# fly.net
KiCad netlist of a schematic drawn in Altium Designer
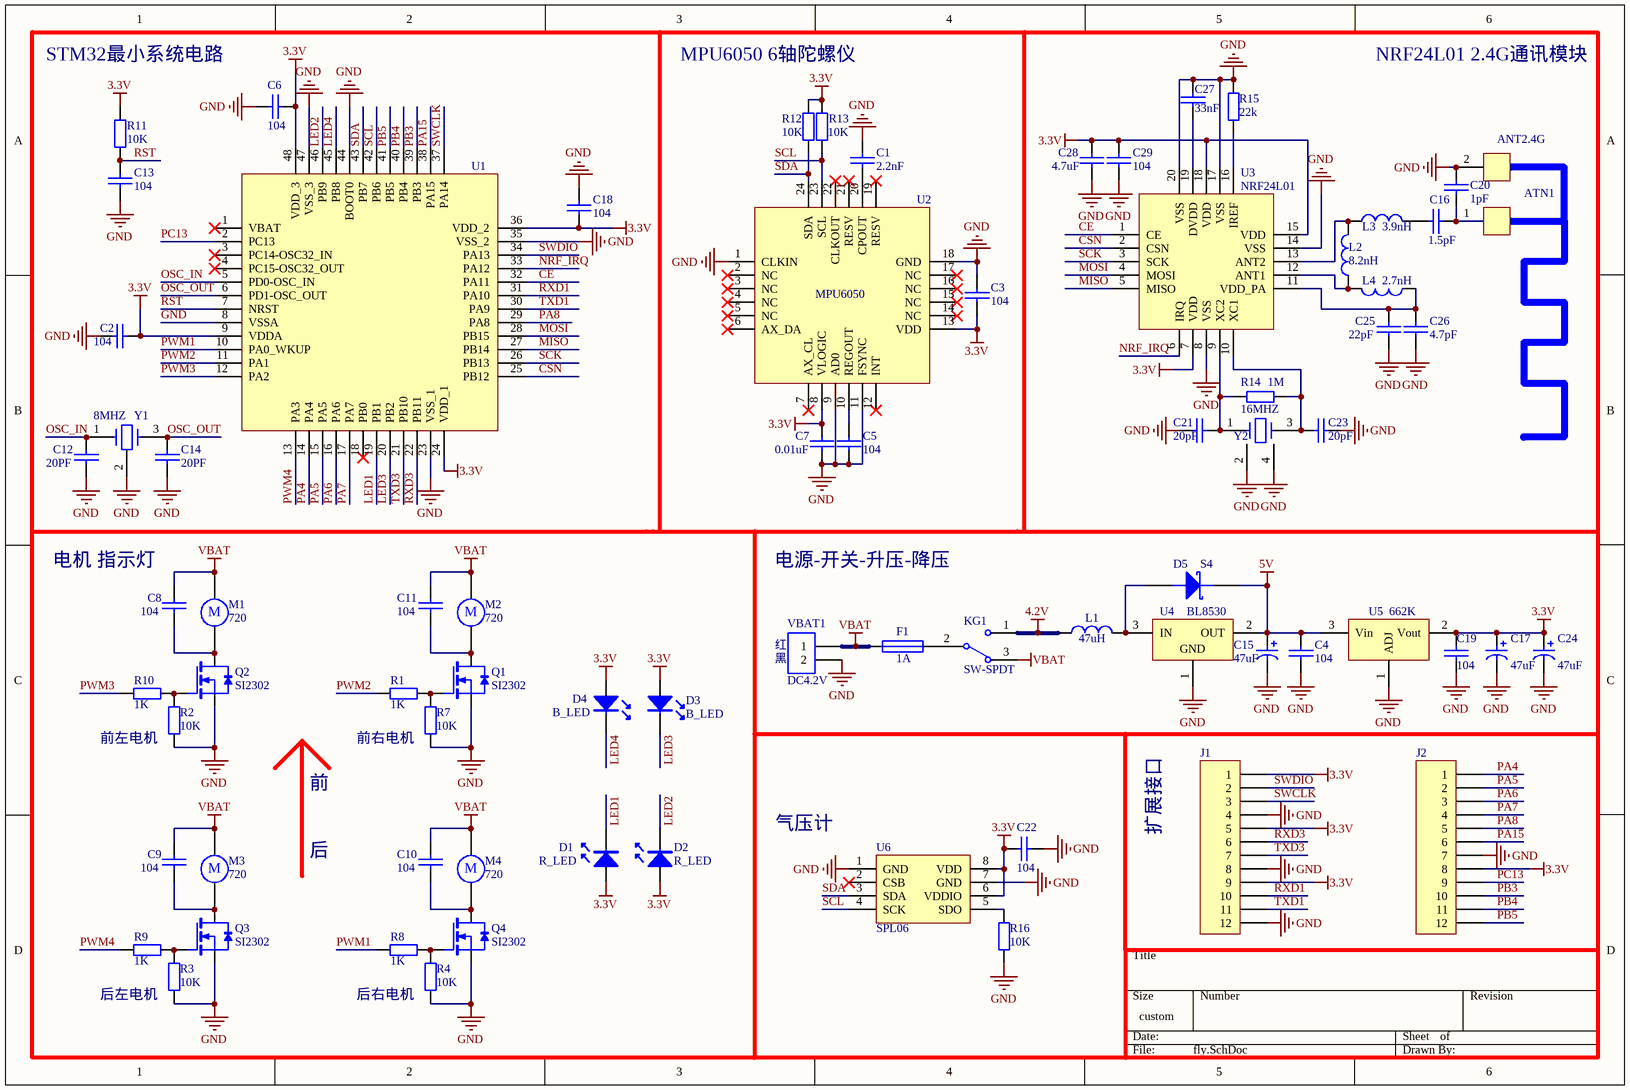
[diagram p0: fly.SchDoc]

(export (version "E")
  (design (tool "Eeschema 10.0.6"))
  (components
    (comp (ref "ATN1") (value "ANT2.4G") (footprint "ANT2.4G_1") (libsource (lib "fly") (part "ANT2.4G_2")))
    (comp (ref "C1")
      (value "2.2nF")
      (footprint "C_0603")
      (description "Capacitor")
      (libsource (lib "fly") (part "CAP"))
    )
    (comp (ref "C2")
      (value "104")
      (footprint "C_0603")
      (description "Capacitor")
      (libsource (lib "fly") (part "CAP"))
    )
    (comp (ref "C3")
      (value "104")
      (footprint "C_0603")
      (description "Capacitor")
      (libsource (lib "fly") (part "CAP"))
    )
    (comp (ref "C4")
      (value "104")
      (footprint "C_0603")
      (description "Capacitor")
      (libsource (lib "fly") (part "CAP"))
    )
    (comp (ref "C5")
      (value "104")
      (footprint "C_0603")
      (description "Capacitor")
      (libsource (lib "fly") (part "CAP"))
    )
    (comp (ref "C6")
      (value "104")
      (footprint "C_0603")
      (description "Capacitor")
      (libsource (lib "fly") (part "CAP"))
    )
    (comp (ref "C7")
      (value "0.01uF")
      (footprint "C_0603")
      (description "Capacitor")
      (libsource (lib "fly") (part "CAP"))
    )
    (comp (ref "C8")
      (value "104")
      (footprint "C_0603")
      (description "Capacitor")
      (libsource (lib "fly") (part "CAP"))
    )
    (comp (ref "C9")
      (value "104")
      (footprint "C_0603")
      (description "Capacitor")
      (libsource (lib "fly") (part "CAP"))
    )
    (comp (ref "C10")
      (value "104")
      (footprint "C_0603")
      (description "Capacitor")
      (libsource (lib "fly") (part "CAP"))
    )
    (comp (ref "C11")
      (value "104")
      (footprint "C_0603")
      (description "Capacitor")
      (libsource (lib "fly") (part "CAP"))
    )
    (comp (ref "C12")
      (value "20PF")
      (footprint "C_0603")
      (description "Capacitor")
      (libsource (lib "fly") (part "CAP"))
    )
    (comp (ref "C13")
      (value "104")
      (footprint "C_0603")
      (description "Capacitor")
      (libsource (lib "fly") (part "CAP"))
    )
    (comp (ref "C14")
      (value "20PF")
      (footprint "C_0603")
      (description "Capacitor")
      (libsource (lib "fly") (part "CAP"))
    )
    (comp (ref "C15")
      (value "47uF")
      (footprint "C_1206")
      (description "Polarized Capacitor (Radial)")
      (fields (field (name "PUBLISHER") "Altium Limited"))
      (libsource (lib "fly") (part "Cap Pol"))
    )
    (comp (ref "C16")
      (value "1.5pF")
      (footprint "C_0603")
      (description "Capacitor")
      (libsource (lib "fly") (part "CAP"))
    )
    (comp (ref "C17")
      (value "47uF")
      (footprint "C_1206")
      (description "Polarized Capacitor (Radial)")
      (fields (field (name "PUBLISHER") "Altium Limited"))
      (libsource (lib "fly") (part "Cap Pol"))
    )
    (comp (ref "C18")
      (value "104")
      (footprint "C_0603")
      (description "Capacitor")
      (libsource (lib "fly") (part "CAP"))
    )
    (comp (ref "C19")
      (value "104")
      (footprint "C_0603")
      (description "Capacitor")
      (libsource (lib "fly") (part "CAP"))
    )
    (comp (ref "C20")
      (value "1pF")
      (footprint "C_0603")
      (description "Capacitor")
      (libsource (lib "fly") (part "CAP"))
    )
    (comp (ref "C21")
      (value "20pF")
      (footprint "C_0603")
      (description "Capacitor")
      (libsource (lib "fly") (part "CAP"))
    )
    (comp (ref "C22")
      (value "104")
      (footprint "C_0603")
      (description "Capacitor")
      (libsource (lib "fly") (part "CAP"))
    )
    (comp (ref "C23")
      (value "20pF")
      (footprint "C_0603")
      (description "Capacitor")
      (libsource (lib "fly") (part "CAP"))
    )
    (comp (ref "C24")
      (value "47uF")
      (footprint "C_1206")
      (description "Polarized Capacitor (Radial)")
      (fields (field (name "PUBLISHER") "Altium Limited"))
      (libsource (lib "fly") (part "Cap Pol"))
    )
    (comp (ref "C25")
      (value "22pF")
      (footprint "C_0603")
      (description "Capacitor")
      (libsource (lib "fly") (part "CAP"))
    )
    (comp (ref "C26")
      (value "4.7pF")
      (footprint "C_0603")
      (description "Capacitor")
      (libsource (lib "fly") (part "CAP"))
    )
    (comp (ref "C27")
      (value "33nF")
      (footprint "C_0603")
      (description "Capacitor")
      (libsource (lib "fly") (part "CAP"))
    )
    (comp (ref "C28")
      (value "4.7uF")
      (footprint "C_0603")
      (description "Capacitor")
      (libsource (lib "fly") (part "CAP"))
    )
    (comp (ref "C29")
      (value "104")
      (footprint "C_0603")
      (description "Capacitor")
      (libsource (lib "fly") (part "CAP"))
    )
    (comp (ref "D1") (value "R_LED") (footprint "LED0603") (libsource (lib "fly") (part "LED")))
    (comp (ref "D2") (value "R_LED") (footprint "LED0603") (libsource (lib "fly") (part "LED")))
    (comp (ref "D3") (value "B_LED") (footprint "LED0603") (libsource (lib "fly") (part "LED")))
    (comp (ref "D4") (value "B_LED") (footprint "LED0603") (libsource (lib "fly") (part "LED")))
    (comp (ref "D5")
      (value "S4")
      (footprint "SOD-123")
      (description "Schottky Diode")
      (libsource (lib "fly") (part "DIODE SCHOTTKY"))
    )
    (comp (ref "F1")
      (value "1A")
      (footprint "FU 0805")
      (description "Fuse")
      (libsource (lib "fly") (part "FUSE1"))
    )
    (comp (ref "J1")
      (value "12P 2.54MM")
      (footprint "HDR2.54-LI-12P")
      (description "Header, 8-Pin")
      (fields (field (name "PUBLISHER") "Altium Limited"))
      (libsource (lib "fly") (part "Header 12"))
    )
    (comp (ref "J2")
      (value "12P 2.54MM")
      (footprint "HDR2.54-LI-12P")
      (description "Header, 8-Pin")
      (fields (field (name "PUBLISHER") "Altium Limited"))
      (libsource (lib "fly") (part "Header 12"))
    )
    (comp (ref "KG1")
      (value "SW-SPDT")
      (footprint "TPKG")
      (description "SPDT Subminiature Toggle Switch, Right Angle Mounting, Vertical Actuation")
      (fields (field (name "PUBLISHER") "Altium Limited"))
      (libsource (lib "fly") (part "SW-SPDT"))
    )
    (comp (ref "L1")
      (value "47uH")
      (footprint "L_CD43")
      (description "Inductor")
      (fields (field (name "PUBLISHER") "Altium Limited"))
      (libsource (lib "fly") (part "Inductor Chip"))
    )
    (comp (ref "L2")
      (value "8.2nH")
      (footprint "L_0603")
      (description "Inductor")
      (fields (field (name "PUBLISHER") "Altium Limited"))
      (libsource (lib "fly") (part "Inductor Chip"))
    )
    (comp (ref "L3")
      (value "3.9nH")
      (footprint "L_0603")
      (description "Inductor")
      (fields (field (name "PUBLISHER") "Altium Limited"))
      (libsource (lib "fly") (part "Inductor Chip"))
    )
    (comp (ref "L4")
      (value "2.7nH")
      (footprint "L_0603")
      (description "Inductor")
      (fields (field (name "PUBLISHER") "Altium Limited"))
      (libsource (lib "fly") (part "Inductor Chip"))
    )
    (comp (ref "M1")
      (value "720")
      (footprint "HDR2.54-LI-2P")
      (description "Motor, General Kind")
      (fields (field (name "PUBLISHER") "Altium Limited"))
      (libsource (lib "fly") (part "Motor"))
    )
    (comp (ref "M2")
      (value "720")
      (footprint "HDR2.54-LI-2P")
      (description "Motor, General Kind")
      (fields (field (name "PUBLISHER") "Altium Limited"))
      (libsource (lib "fly") (part "Motor"))
    )
    (comp (ref "M3")
      (value "720")
      (footprint "HDR2.54-LI-2P")
      (description "Motor, General Kind")
      (fields (field (name "PUBLISHER") "Altium Limited"))
      (libsource (lib "fly") (part "Motor"))
    )
    (comp (ref "M4")
      (value "720")
      (footprint "HDR2.54-LI-2P")
      (description "Motor, General Kind")
      (fields (field (name "PUBLISHER") "Altium Limited"))
      (libsource (lib "fly") (part "Motor"))
    )
    (comp (ref "Q1")
      (value "SI2302")
      (footprint "SOT23")
      (description "N-Channel MOSFET")
      (libsource (lib "fly") (part "N_MOS"))
    )
    (comp (ref "Q2")
      (value "SI2302")
      (footprint "SOT23")
      (description "N-Channel MOSFET")
      (libsource (lib "fly") (part "N_MOS"))
    )
    (comp (ref "Q3")
      (value "SI2302")
      (footprint "SOT23")
      (description "N-Channel MOSFET")
      (libsource (lib "fly") (part "N_MOS"))
    )
    (comp (ref "Q4")
      (value "SI2302")
      (footprint "SOT23")
      (description "N-Channel MOSFET")
      (libsource (lib "fly") (part "N_MOS"))
    )
    (comp (ref "R1")
      (value "1K")
      (footprint "R_0603")
      (description "Resistor")
      (fields (field (name "PUBLISHER") "Altium Limited"))
      (libsource (lib "") (part "Res2_1"))
    )
    (comp (ref "R2")
      (value "10K")
      (footprint "R_0603")
      (description "Resistor")
      (fields (field (name "PUBLISHER") "Altium Limited"))
      (libsource (lib "fly") (part "Res2"))
    )
    (comp (ref "R3")
      (value "10K")
      (footprint "R_0603")
      (description "Resistor")
      (fields (field (name "PUBLISHER") "Altium Limited"))
      (libsource (lib "fly") (part "Res2"))
    )
    (comp (ref "R4")
      (value "10K")
      (footprint "R_0603")
      (description "Resistor")
      (fields (field (name "PUBLISHER") "Altium Limited"))
      (libsource (lib "fly") (part "Res2"))
    )
    (comp (ref "R7")
      (value "10K")
      (footprint "R_0603")
      (description "Resistor")
      (fields (field (name "PUBLISHER") "Altium Limited"))
      (libsource (lib "fly") (part "Res2"))
    )
    (comp (ref "R8")
      (value "1K")
      (footprint "R_0603")
      (description "Resistor")
      (fields (field (name "PUBLISHER") "Altium Limited"))
      (libsource (lib "") (part "Res2_1"))
    )
    (comp (ref "R9")
      (value "1K")
      (footprint "R_0603")
      (description "Resistor")
      (fields (field (name "PUBLISHER") "Altium Limited"))
      (libsource (lib "") (part "Res2_1"))
    )
    (comp (ref "R10")
      (value "1K")
      (footprint "R_0603")
      (description "Resistor")
      (fields (field (name "PUBLISHER") "Altium Limited"))
      (libsource (lib "") (part "Res2_1"))
    )
    (comp (ref "R11")
      (value "10K")
      (footprint "R_0603")
      (description "Resistor")
      (fields (field (name "PUBLISHER") "Altium Limited"))
      (libsource (lib "fly") (part "Res2"))
    )
    (comp (ref "R12")
      (value "10K")
      (footprint "R_0603")
      (description "Resistor")
      (fields (field (name "PUBLISHER") "Altium Limited"))
      (libsource (lib "fly") (part "Res2"))
    )
    (comp (ref "R13")
      (value "10K")
      (footprint "R_0603")
      (description "Resistor")
      (fields (field (name "PUBLISHER") "Altium Limited"))
      (libsource (lib "fly") (part "Res2"))
    )
    (comp (ref "R14")
      (value "1M")
      (footprint "R_0603")
      (description "Resistor")
      (fields (field (name "PUBLISHER") "Altium Limited"))
      (libsource (lib "") (part "Res2_1"))
    )
    (comp (ref "R15")
      (value "22k")
      (footprint "R_0603")
      (description "Resistor")
      (fields (field (name "PUBLISHER") "Altium Limited"))
      (libsource (lib "fly") (part "Res2"))
    )
    (comp (ref "R16")
      (value "10K")
      (footprint "R_0603")
      (description "Resistor")
      (fields (field (name "PUBLISHER") "Altium Limited"))
      (libsource (lib "") (part "Res2_2"))
    )
    (comp (ref "U1")
      (value "STM32F103C8T6_LQFP48")
      (footprint "LQFP48_STM32")
      (libsource (lib "fly") (part "STM32_LQFP48"))
    )
    (comp (ref "U2") (value "MPU6050") (footprint "QFN24") (libsource (lib "fly") (part "MPU6050")))
    (comp (ref "U3") (value "NRF24L01") (footprint "LQFP32") (libsource (lib "fly") (part "NRF24L01")))
    (comp (ref "U4")
      (value "BL8530")
      (footprint "SOT-89")
      (description "POSITIVE OUTPUT VOLTAGE")
      (libsource (lib "fly") (part "HT7750"))
    )
    (comp (ref "U5")
      (value "662K")
      (footprint "SOT23-PIN132")
      (description "3-Terminal Adjustable Positive Voltage Regulator")
      (libsource (lib "fly") (part "LM317"))
    )
    (comp (ref "U6") (value "SPL06") (footprint "SMD_SPL06") (libsource (lib "fly") (part "SPL06")))
    (comp (ref "VBAT1")
      (value "DC4.2V")
      (footprint "HDR2.54-WI-2P")
      (description "Connector")
      (libsource (lib "fly") (part "CON2"))
    )
    (comp (ref "Y1") (value "8MHZ") (footprint "Y3213") (libsource (lib "fly") (part "Y")))
    (comp (ref "Y2") (value "16MHZ") (footprint "OSC 3225-4P") (libsource (lib "fly") (part "Y_1")))
  )
  (nets
    (net (code "1") (name "/CE") (class "Default")
      (node (ref "U1") (pin "32") (pinfunction "PA11_32") (pintype "passive"))
      (node (ref "U3") (pin "1") (pinfunction "CE_1") (pintype "power_in"))
    )
    (net (code "2") (name "/CSN") (class "Default")
      (node (ref "U1") (pin "25") (pinfunction "PB12_25") (pintype "passive"))
      (node (ref "U3") (pin "2") (pinfunction "CSN_2") (pintype "power_in"))
    )
    (net (code "3") (name "/LED1") (class "Default")
      (node (ref "D1") (pin "2") (pinfunction "2_2") (pintype "passive"))
      (node (ref "U1") (pin "19") (pinfunction "PB1_19") (pintype "passive"))
    )
    (net (code "4") (name "/LED2") (class "Default")
      (node (ref "D2") (pin "2") (pinfunction "2_2") (pintype "passive"))
      (node (ref "U1") (pin "46") (pinfunction "PB9_46") (pintype "passive"))
    )
    (net (code "5") (name "/LED3") (class "Default")
      (node (ref "D3") (pin "2") (pinfunction "2_2") (pintype "passive"))
      (node (ref "U1") (pin "20") (pinfunction "PB2_20") (pintype "passive"))
    )
    (net (code "6") (name "/LED4") (class "Default")
      (node (ref "D4") (pin "2") (pinfunction "2_2") (pintype "passive"))
      (node (ref "U1") (pin "45") (pinfunction "PB8_45") (pintype "passive"))
    )
    (net (code "7") (name "/MISO") (class "Default")
      (node (ref "U1") (pin "27") (pinfunction "PB14_27") (pintype "passive"))
      (node (ref "U3") (pin "5") (pinfunction "MISO_5") (pintype "power_in"))
    )
    (net (code "8") (name "/MOSI") (class "Default")
      (node (ref "U1") (pin "28") (pinfunction "PB15_28") (pintype "passive"))
      (node (ref "U3") (pin "4") (pinfunction "MOSI_4") (pintype "power_in"))
    )
    (net (code "9") (name "/NRF_IRQ") (class "Default")
      (node (ref "U1") (pin "33") (pinfunction "PA12_33") (pintype "passive"))
      (node (ref "U3") (pin "6") (pinfunction "IRQ_6") (pintype "power_in"))
    )
    (net (code "10") (name "/OSC_IN") (class "Default")
      (node (ref "C12") (pin "1") (pinfunction "1_1") (pintype "passive"))
      (node (ref "U1") (pin "5") (pinfunction "PD0-OSC_IN_5") (pintype "passive"))
      (node (ref "Y1") (pin "1") (pinfunction "1_1") (pintype "passive"))
    )
    (net (code "11") (name "/OSC_OUT") (class "Default")
      (node (ref "C14") (pin "2") (pinfunction "2_2") (pintype "passive"))
      (node (ref "U1") (pin "6") (pinfunction "PD1-OSC_OUT_6") (pintype "passive"))
      (node (ref "Y1") (pin "3") (pinfunction "3_3") (pintype "passive"))
    )
    (net (code "12") (name "/PA4") (class "Default")
      (node (ref "J2") (pin "1") (pinfunction "1_1") (pintype "passive"))
      (node (ref "U1") (pin "14") (pinfunction "PA4_14") (pintype "passive"))
    )
    (net (code "13") (name "/PA5") (class "Default")
      (node (ref "J2") (pin "2") (pinfunction "2_2") (pintype "passive"))
      (node (ref "U1") (pin "15") (pinfunction "PA5_15") (pintype "passive"))
    )
    (net (code "14") (name "/PA6") (class "Default")
      (node (ref "J2") (pin "3") (pinfunction "3_3") (pintype "passive"))
      (node (ref "U1") (pin "16") (pinfunction "PA6_16") (pintype "passive"))
    )
    (net (code "15") (name "/PA7") (class "Default")
      (node (ref "J2") (pin "4") (pinfunction "4_4") (pintype "passive"))
      (node (ref "U1") (pin "17") (pinfunction "PA7_17") (pintype "passive"))
    )
    (net (code "16") (name "/PA8") (class "Default")
      (node (ref "J2") (pin "5") (pinfunction "5_5") (pintype "passive"))
      (node (ref "U1") (pin "29") (pinfunction "PA8_29") (pintype "passive"))
    )
    (net (code "17") (name "/PA15") (class "Default")
      (node (ref "J2") (pin "6") (pinfunction "6_6") (pintype "passive"))
      (node (ref "U1") (pin "38") (pinfunction "PA15_38") (pintype "passive"))
    )
    (net (code "18") (name "/PB3") (class "Default")
      (node (ref "J2") (pin "10") (pinfunction "10_10") (pintype "passive"))
      (node (ref "U1") (pin "39") (pinfunction "PB3_39") (pintype "passive"))
    )
    (net (code "19") (name "/PB4") (class "Default")
      (node (ref "J2") (pin "11") (pinfunction "11_11") (pintype "passive"))
      (node (ref "U1") (pin "40") (pinfunction "PB4_40") (pintype "passive"))
    )
    (net (code "20") (name "/PB5") (class "Default")
      (node (ref "J2") (pin "12") (pinfunction "12_12") (pintype "passive"))
      (node (ref "U1") (pin "41") (pinfunction "PB5_41") (pintype "passive"))
    )
    (net (code "21") (name "/PC13") (class "Default")
      (node (ref "J2") (pin "9") (pinfunction "9_9") (pintype "passive"))
      (node (ref "U1") (pin "2") (pinfunction "PC13_2") (pintype "passive"))
    )
    (net (code "22") (name "/PWM1") (class "Default")
      (node (ref "R8") (pin "2") (pinfunction "2_2") (pintype "passive"))
      (node (ref "U1") (pin "10") (pinfunction "PA0_WKUP_10") (pintype "passive"))
    )
    (net (code "23") (name "/PWM2") (class "Default")
      (node (ref "R1") (pin "2") (pinfunction "2_2") (pintype "passive"))
      (node (ref "U1") (pin "11") (pinfunction "PA1_11") (pintype "passive"))
    )
    (net (code "24") (name "/PWM3") (class "Default")
      (node (ref "R10") (pin "2") (pinfunction "2_2") (pintype "passive"))
      (node (ref "U1") (pin "12") (pinfunction "PA2_12") (pintype "passive"))
    )
    (net (code "25") (name "/PWM4") (class "Default")
      (node (ref "R9") (pin "2") (pinfunction "2_2") (pintype "passive"))
      (node (ref "U1") (pin "13") (pinfunction "PA3_13") (pintype "passive"))
    )
    (net (code "26") (name "/RST") (class "Default")
      (node (ref "C13") (pin "1") (pinfunction "1_1") (pintype "passive"))
      (node (ref "R11") (pin "1") (pinfunction "1_1") (pintype "passive"))
      (node (ref "U1") (pin "7") (pinfunction "NRST_7") (pintype "passive"))
    )
    (net (code "27") (name "/RXD1") (class "Default")
      (node (ref "J1") (pin "10") (pinfunction "10_10") (pintype "passive"))
      (node (ref "U1") (pin "31") (pinfunction "PA10_31") (pintype "passive"))
    )
    (net (code "28") (name "/RXD3") (class "Default")
      (node (ref "J1") (pin "6") (pinfunction "6_6") (pintype "passive"))
      (node (ref "U1") (pin "22") (pinfunction "PB11_22") (pintype "passive"))
    )
    (net (code "29") (name "/SCK") (class "Default")
      (node (ref "U1") (pin "26") (pinfunction "PB13_26") (pintype "passive"))
      (node (ref "U3") (pin "3") (pinfunction "SCK_3") (pintype "power_in"))
    )
    (net (code "30") (name "/SCL") (class "Default")
      (node (ref "R13") (pin "1") (pinfunction "1_1") (pintype "passive"))
      (node (ref "U1") (pin "42") (pinfunction "PB6_42") (pintype "passive"))
      (node (ref "U2") (pin "23") (pinfunction "SCL_23") (pintype "passive"))
      (node (ref "U6") (pin "4") (pinfunction "SCK_4") (pintype "power_in"))
    )
    (net (code "31") (name "/SDA") (class "Default")
      (node (ref "R12") (pin "1") (pinfunction "1_1") (pintype "passive"))
      (node (ref "U1") (pin "43") (pinfunction "PB7_43") (pintype "passive"))
      (node (ref "U2") (pin "24") (pinfunction "SDA_24") (pintype "passive"))
      (node (ref "U6") (pin "3") (pinfunction "SDA_3") (pintype "power_in"))
    )
    (net (code "32") (name "/SWCLK") (class "Default")
      (node (ref "J1") (pin "3") (pinfunction "3_3") (pintype "passive"))
      (node (ref "U1") (pin "37") (pinfunction "PA14_37") (pintype "passive"))
    )
    (net (code "33") (name "/SWDIO") (class "Default")
      (node (ref "J1") (pin "2") (pinfunction "2_2") (pintype "passive"))
      (node (ref "U1") (pin "34") (pinfunction "PA13_34") (pintype "passive"))
    )
    (net (code "34") (name "/TXD1") (class "Default")
      (node (ref "J1") (pin "11") (pinfunction "11_11") (pintype "passive"))
      (node (ref "U1") (pin "30") (pinfunction "PA9_30") (pintype "passive"))
    )
    (net (code "35") (name "/TXD3") (class "Default")
      (node (ref "J1") (pin "7") (pinfunction "7_7") (pintype "passive"))
      (node (ref "U1") (pin "21") (pinfunction "PB10_21") (pintype "passive"))
    )
    (net (code "36") (name "3.3V") (class "Default")
      (node (ref "C17") (pin "1") (pinfunction "1_1") (pintype "passive"))
      (node (ref "C18") (pin "1") (pinfunction "1_1") (pintype "passive"))
      (node (ref "C19") (pin "2") (pinfunction "2_2") (pintype "passive"))
      (node (ref "C2") (pin "2") (pinfunction "2_2") (pintype "passive"))
      (node (ref "C22") (pin "1") (pinfunction "1_1") (pintype "passive"))
      (node (ref "C24") (pin "1") (pinfunction "1_1") (pintype "passive"))
      (node (ref "C28") (pin "2") (pinfunction "2_2") (pintype "passive"))
      (node (ref "C29") (pin "2") (pinfunction "2_2") (pintype "passive"))
      (node (ref "C3") (pin "1") (pinfunction "1_1") (pintype "passive"))
      (node (ref "C6") (pin "1") (pinfunction "1_1") (pintype "passive"))
      (node (ref "C7") (pin "2") (pinfunction "2_2") (pintype "passive"))
      (node (ref "D1") (pin "1") (pinfunction "1_1") (pintype "passive"))
      (node (ref "D2") (pin "1") (pinfunction "1_1") (pintype "passive"))
      (node (ref "D3") (pin "1") (pinfunction "1_1") (pintype "passive"))
      (node (ref "D4") (pin "1") (pinfunction "1_1") (pintype "passive"))
      (node (ref "J1") (pin "1") (pinfunction "1_1") (pintype "passive"))
      (node (ref "J1") (pin "5") (pinfunction "5_5") (pintype "passive"))
      (node (ref "J1") (pin "9") (pinfunction "9_9") (pintype "passive"))
      (node (ref "J2") (pin "8") (pinfunction "8_8") (pintype "passive"))
      (node (ref "R11") (pin "2") (pinfunction "2_2") (pintype "passive"))
      (node (ref "R12") (pin "2") (pinfunction "2_2") (pintype "passive"))
      (node (ref "R13") (pin "2") (pinfunction "2_2") (pintype "passive"))
      (node (ref "U1") (pin "24") (pinfunction "VDD_1_24") (pintype "passive"))
      (node (ref "U1") (pin "36") (pinfunction "VDD_2_36") (pintype "passive"))
      (node (ref "U1") (pin "48") (pinfunction "VDD_3_48") (pintype "passive"))
      (node (ref "U1") (pin "9") (pinfunction "VDDA_9") (pintype "passive"))
      (node (ref "U2") (pin "13") (pinfunction "VDD_13") (pintype "passive"))
      (node (ref "U2") (pin "8") (pinfunction "VLOGIC_8") (pintype "passive"))
      (node (ref "U3") (pin "15") (pinfunction "VDD_15") (pintype "power_in"))
      (node (ref "U3") (pin "18") (pinfunction "VDD_18") (pintype "power_in"))
      (node (ref "U3") (pin "7") (pinfunction "VDD_7") (pintype "power_in"))
      (node (ref "U5") (pin "2") (pinfunction "Vout_2") (pintype "passive"))
      (node (ref "U6") (pin "6") (pinfunction "VDDIO_6") (pintype "power_in"))
      (node (ref "U6") (pin "8") (pinfunction "VDD_8") (pintype "power_in"))
    )
    (net (code "37") (name "4.2V") (class "Default")
      (node (ref "KG1") (pin "1") (pinfunction "1_1") (pintype "passive"))
      (node (ref "L1") (pin "1") (pinfunction "1_1") (pintype "passive"))
    )
    (net (code "38") (name "5V") (class "Default")
      (node (ref "C15") (pin "1") (pinfunction "1_1") (pintype "passive"))
      (node (ref "C4") (pin "2") (pinfunction "2_2") (pintype "passive"))
      (node (ref "D5") (pin "2") (pinfunction "K_2") (pintype "passive"))
      (node (ref "U4") (pin "2") (pinfunction "OUT_2") (pintype "power_in"))
      (node (ref "U5") (pin "3") (pinfunction "Vin_3") (pintype "passive"))
    )
    (net (code "39") (name "GND") (class "Default")
      (node (ref "ATN1") (pin "2") (pintype "passive"))
      (node (ref "C1") (pin "2") (pinfunction "2_2") (pintype "passive"))
      (node (ref "C12") (pin "2") (pinfunction "2_2") (pintype "passive"))
      (node (ref "C13") (pin "2") (pinfunction "2_2") (pintype "passive"))
      (node (ref "C14") (pin "1") (pinfunction "1_1") (pintype "passive"))
      (node (ref "C15") (pin "2") (pinfunction "2_2") (pintype "passive"))
      (node (ref "C17") (pin "2") (pinfunction "2_2") (pintype "passive"))
      (node (ref "C18") (pin "2") (pinfunction "2_2") (pintype "passive"))
      (node (ref "C19") (pin "1") (pinfunction "1_1") (pintype "passive"))
      (node (ref "C2") (pin "1") (pinfunction "1_1") (pintype "passive"))
      (node (ref "C20") (pin "2") (pinfunction "2_2") (pintype "passive"))
      (node (ref "C21") (pin "1") (pinfunction "1_1") (pintype "passive"))
      (node (ref "C22") (pin "2") (pinfunction "2_2") (pintype "passive"))
      (node (ref "C23") (pin "2") (pinfunction "2_2") (pintype "passive"))
      (node (ref "C24") (pin "2") (pinfunction "2_2") (pintype "passive"))
      (node (ref "C25") (pin "2") (pinfunction "2_2") (pintype "passive"))
      (node (ref "C26") (pin "2") (pinfunction "2_2") (pintype "passive"))
      (node (ref "C27") (pin "1") (pinfunction "1_1") (pintype "passive"))
      (node (ref "C28") (pin "1") (pinfunction "1_1") (pintype "passive"))
      (node (ref "C29") (pin "1") (pinfunction "1_1") (pintype "passive"))
      (node (ref "C3") (pin "2") (pinfunction "2_2") (pintype "passive"))
      (node (ref "C4") (pin "1") (pinfunction "1_1") (pintype "passive"))
      (node (ref "C5") (pin "1") (pinfunction "1_1") (pintype "passive"))
      (node (ref "C6") (pin "2") (pinfunction "2_2") (pintype "passive"))
      (node (ref "C7") (pin "1") (pinfunction "1_1") (pintype "passive"))
      (node (ref "J1") (pin "12") (pinfunction "12_12") (pintype "passive"))
      (node (ref "J1") (pin "4") (pinfunction "4_4") (pintype "passive"))
      (node (ref "J1") (pin "8") (pinfunction "8_8") (pintype "passive"))
      (node (ref "J2") (pin "7") (pinfunction "7_7") (pintype "passive"))
      (node (ref "Q1") (pin "3") (pinfunction "S_3") (pintype "passive"))
      (node (ref "Q2") (pin "3") (pinfunction "S_3") (pintype "passive"))
      (node (ref "Q3") (pin "3") (pinfunction "S_3") (pintype "passive"))
      (node (ref "Q4") (pin "3") (pinfunction "S_3") (pintype "passive"))
      (node (ref "R15") (pin "2") (pinfunction "2_2") (pintype "passive"))
      (node (ref "R16") (pin "1") (pinfunction "1_1") (pintype "passive"))
      (node (ref "R2") (pin "1") (pinfunction "1_1") (pintype "passive"))
      (node (ref "R3") (pin "1") (pinfunction "1_1") (pintype "passive"))
      (node (ref "R4") (pin "1") (pinfunction "1_1") (pintype "passive"))
      (node (ref "R7") (pin "1") (pinfunction "1_1") (pintype "passive"))
      (node (ref "U1") (pin "23") (pinfunction "VSS_1_23") (pintype "passive"))
      (node (ref "U1") (pin "35") (pinfunction "VSS_2_35") (pintype "passive"))
      (node (ref "U1") (pin "44") (pinfunction "BOOT0_44") (pintype "passive"))
      (node (ref "U1") (pin "47") (pinfunction "VSS_3_47") (pintype "passive"))
      (node (ref "U1") (pin "8") (pinfunction "VSSA_8") (pintype "passive"))
      (node (ref "U2") (pin "1") (pinfunction "CLKIN_1") (pintype "passive"))
      (node (ref "U2") (pin "11") (pinfunction "FSYNC_11") (pintype "passive"))
      (node (ref "U2") (pin "18") (pinfunction "GND_18") (pintype "passive"))
      (node (ref "U2") (pin "9") (pinfunction "AD0_9") (pintype "passive"))
      (node (ref "U3") (pin "14") (pinfunction "VSS_14") (pintype "power_in"))
      (node (ref "U3") (pin "17") (pinfunction "VSS_17") (pintype "power_in"))
      (node (ref "U3") (pin "20") (pinfunction "VSS_20") (pintype "power_in"))
      (node (ref "U3") (pin "8") (pinfunction "VSS_8") (pintype "power_in"))
      (node (ref "U4") (pin "1") (pinfunction "GND_1") (pintype "power_in"))
      (node (ref "U5") (pin "1") (pinfunction "ADJ_1") (pintype "passive"))
      (node (ref "U6") (pin "1") (pinfunction "GND_1") (pintype "power_in"))
      (node (ref "U6") (pin "7") (pinfunction "GND_7") (pintype "power_in"))
      (node (ref "VBAT1") (pin "1") (pinfunction "2_1") (pintype "passive"))
      (node (ref "Y1") (pin "2") (pinfunction "2_2") (pintype "passive"))
      (node (ref "Y2") (pin "2") (pinfunction "2_2") (pintype "passive"))
      (node (ref "Y2") (pin "4") (pinfunction "4_4") (pintype "passive"))
    )
    (net (code "40") (name "Net-(ATN1-Pad1)") (class "Default")
      (node (ref "ATN1") (pin "1") (pintype "passive"))
      (node (ref "C16") (pin "1") (pinfunction "1_1") (pintype "passive"))
      (node (ref "C20") (pin "1") (pinfunction "1_1") (pintype "passive"))
    )
    (net (code "41") (name "Net-(C16-Pad2)") (class "Default")
      (node (ref "C16") (pin "2") (pinfunction "2_2") (pintype "passive"))
      (node (ref "L3") (pin "2") (pinfunction "2_2") (pintype "passive"))
    )
    (net (code "42") (name "Net-(D5-A)") (class "Default")
      (node (ref "D5") (pin "1") (pinfunction "A_1") (pintype "passive"))
      (node (ref "L1") (pin "2") (pinfunction "2_2") (pintype "passive"))
      (node (ref "U4") (pin "3") (pinfunction "IN_3") (pintype "power_in"))
    )
    (net (code "43") (name "Net-(F1-Pad2)") (class "Default")
      (node (ref "F1") (pin "2") (pinfunction "2_2") (pintype "passive"))
      (node (ref "KG1") (pin "2") (pinfunction "2_2") (pintype "passive"))
    )
    (net (code "44") (name "Net-(Q1-D)") (class "Default")
      (node (ref "C11") (pin "1") (pinfunction "1_1") (pintype "passive"))
      (node (ref "M2") (pin "2") (pinfunction "2_2") (pintype "passive"))
      (node (ref "Q1") (pin "2") (pinfunction "D_2") (pintype "passive"))
    )
    (net (code "45") (name "Net-(Q1-G)") (class "Default")
      (node (ref "Q1") (pin "1") (pinfunction "G_1") (pintype "passive"))
      (node (ref "R1") (pin "1") (pinfunction "1_1") (pintype "passive"))
      (node (ref "R7") (pin "2") (pinfunction "2_2") (pintype "passive"))
    )
    (net (code "46") (name "Net-(Q2-D)") (class "Default")
      (node (ref "C8") (pin "1") (pinfunction "1_1") (pintype "passive"))
      (node (ref "M1") (pin "2") (pinfunction "2_2") (pintype "passive"))
      (node (ref "Q2") (pin "2") (pinfunction "D_2") (pintype "passive"))
    )
    (net (code "47") (name "Net-(Q2-G)") (class "Default")
      (node (ref "Q2") (pin "1") (pinfunction "G_1") (pintype "passive"))
      (node (ref "R10") (pin "1") (pinfunction "1_1") (pintype "passive"))
      (node (ref "R2") (pin "2") (pinfunction "2_2") (pintype "passive"))
    )
    (net (code "48") (name "Net-(Q3-D)") (class "Default")
      (node (ref "C9") (pin "1") (pinfunction "1_1") (pintype "passive"))
      (node (ref "M3") (pin "2") (pinfunction "2_2") (pintype "passive"))
      (node (ref "Q3") (pin "2") (pinfunction "D_2") (pintype "passive"))
    )
    (net (code "49") (name "Net-(Q3-G)") (class "Default")
      (node (ref "Q3") (pin "1") (pinfunction "G_1") (pintype "passive"))
      (node (ref "R3") (pin "2") (pinfunction "2_2") (pintype "passive"))
      (node (ref "R9") (pin "1") (pinfunction "1_1") (pintype "passive"))
    )
    (net (code "50") (name "Net-(Q4-D)") (class "Default")
      (node (ref "C10") (pin "1") (pinfunction "1_1") (pintype "passive"))
      (node (ref "M4") (pin "2") (pinfunction "2_2") (pintype "passive"))
      (node (ref "Q4") (pin "2") (pinfunction "D_2") (pintype "passive"))
    )
    (net (code "51") (name "Net-(Q4-G)") (class "Default")
      (node (ref "Q4") (pin "1") (pinfunction "G_1") (pintype "passive"))
      (node (ref "R4") (pin "2") (pinfunction "2_2") (pintype "passive"))
      (node (ref "R8") (pin "1") (pinfunction "1_1") (pintype "passive"))
    )
    (net (code "52") (name "Net-(U2-CPOUT)") (class "Default")
      (node (ref "C1") (pin "1") (pinfunction "1_1") (pintype "passive"))
      (node (ref "U2") (pin "20") (pinfunction "CPOUT_20") (pintype "passive"))
    )
    (net (code "53") (name "Net-(U2-REGOUT)") (class "Default")
      (node (ref "C5") (pin "2") (pinfunction "2_2") (pintype "passive"))
      (node (ref "U2") (pin "10") (pinfunction "REGOUT_10") (pintype "passive"))
    )
    (net (code "54") (name "Net-(U3-ANT1)") (class "Default")
      (node (ref "L2") (pin "1") (pinfunction "1_1") (pintype "passive"))
      (node (ref "L4") (pin "2") (pinfunction "2_2") (pintype "passive"))
      (node (ref "U3") (pin "12") (pinfunction "ANT1_12") (pintype "power_in"))
    )
    (net (code "55") (name "Net-(U3-ANT2)") (class "Default")
      (node (ref "L2") (pin "2") (pinfunction "2_2") (pintype "passive"))
      (node (ref "L3") (pin "1") (pinfunction "1_1") (pintype "passive"))
      (node (ref "U3") (pin "13") (pinfunction "ANT2_13") (pintype "power_in"))
    )
    (net (code "56") (name "Net-(U3-DVDD)") (class "Default")
      (node (ref "C27") (pin "2") (pinfunction "2_2") (pintype "passive"))
      (node (ref "U3") (pin "19") (pinfunction "DVDD_19") (pintype "power_in"))
    )
    (net (code "57") (name "Net-(U3-IREF)") (class "Default")
      (node (ref "R15") (pin "1") (pinfunction "1_1") (pintype "passive"))
      (node (ref "U3") (pin "16") (pinfunction "IREF_16") (pintype "power_in"))
    )
    (net (code "58") (name "Net-(U3-VDD_PA)") (class "Default")
      (node (ref "C25") (pin "1") (pinfunction "1_1") (pintype "passive"))
      (node (ref "C26") (pin "1") (pinfunction "1_1") (pintype "passive"))
      (node (ref "L4") (pin "1") (pinfunction "1_1") (pintype "passive"))
      (node (ref "U3") (pin "11") (pinfunction "VDD_PA_11") (pintype "power_in"))
    )
    (net (code "59") (name "Net-(U3-XC1)") (class "Default")
      (node (ref "C23") (pin "1") (pinfunction "1_1") (pintype "passive"))
      (node (ref "R14") (pin "1") (pinfunction "1_1") (pintype "passive"))
      (node (ref "U3") (pin "10") (pinfunction "XC1_10") (pintype "power_in"))
      (node (ref "Y2") (pin "3") (pinfunction "3_3") (pintype "passive"))
    )
    (net (code "60") (name "Net-(U3-XC2)") (class "Default")
      (node (ref "C21") (pin "2") (pinfunction "2_2") (pintype "passive"))
      (node (ref "R14") (pin "2") (pinfunction "2_2") (pintype "passive"))
      (node (ref "U3") (pin "9") (pinfunction "XC2_9") (pintype "power_in"))
      (node (ref "Y2") (pin "1") (pinfunction "1_1") (pintype "passive"))
    )
    (net (code "61") (name "Net-(U6-SDO)") (class "Default")
      (node (ref "R16") (pin "2") (pinfunction "2_2") (pintype "passive"))
      (node (ref "U6") (pin "5") (pinfunction "SDO_5") (pintype "power_in"))
    )
    (net (code "62") (name "VBAT") (class "Default")
      (node (ref "C10") (pin "2") (pinfunction "2_2") (pintype "passive"))
      (node (ref "C11") (pin "2") (pinfunction "2_2") (pintype "passive"))
      (node (ref "C8") (pin "2") (pinfunction "2_2") (pintype "passive"))
      (node (ref "C9") (pin "2") (pinfunction "2_2") (pintype "passive"))
      (node (ref "F1") (pin "1") (pinfunction "1_1") (pintype "passive"))
      (node (ref "KG1") (pin "3") (pinfunction "3_3") (pintype "passive"))
      (node (ref "M1") (pin "1") (pinfunction "1_1") (pintype "passive"))
      (node (ref "M2") (pin "1") (pinfunction "1_1") (pintype "passive"))
      (node (ref "M3") (pin "1") (pinfunction "1_1") (pintype "passive"))
      (node (ref "M4") (pin "1") (pinfunction "1_1") (pintype "passive"))
      (node (ref "VBAT1") (pin "2") (pinfunction "1_2") (pintype "passive"))
    )
    (net (code "63") (name "unconnected-(U1-PB0-Pad18)") (class "Default")
      (node (ref "U1") (pin "18") (pinfunction "PB0_18") (pintype "passive+no_connect"))
    )
    (net (code "64") (name "unconnected-(U1-PC14-OSC32_IN-Pad3)") (class "Default")
      (node (ref "U1") (pin "3") (pinfunction "PC14-OSC32_IN_3") (pintype "passive+no_connect"))
    )
    (net (code "65") (name "unconnected-(U1-PC15-OSC32_OUT-Pad4)") (class "Default")
      (node (ref "U1") (pin "4") (pinfunction "PC15-OSC32_OUT_4") (pintype "passive+no_connect"))
    )
    (net (code "66") (name "unconnected-(U1-VBAT-Pad1)") (class "Default")
      (node (ref "U1") (pin "1") (pinfunction "VBAT_1") (pintype "passive+no_connect"))
    )
    (net (code "67") (name "unconnected-(U2-AX_CL-Pad7)") (class "Default")
      (node (ref "U2") (pin "7") (pinfunction "AX_CL_7") (pintype "passive+no_connect"))
    )
    (net (code "68") (name "unconnected-(U2-AX_DA-Pad6)") (class "Default")
      (node (ref "U2") (pin "6") (pinfunction "AX_DA_6") (pintype "passive+no_connect"))
    )
    (net (code "69") (name "unconnected-(U2-CLKOUT-Pad22)") (class "Default")
      (node (ref "U2") (pin "22") (pinfunction "CLKOUT_22") (pintype "passive+no_connect"))
    )
    (net (code "70") (name "unconnected-(U2-INT-Pad12)") (class "Default")
      (node (ref "U2") (pin "12") (pinfunction "INT_12") (pintype "passive+no_connect"))
    )
    (net (code "71") (name "unconnected-(U2-NC-Pad2)") (class "Default")
      (node (ref "U2") (pin "2") (pinfunction "NC_2") (pintype "passive+no_connect"))
    )
    (net (code "72") (name "unconnected-(U2-NC-Pad3)") (class "Default")
      (node (ref "U2") (pin "3") (pinfunction "NC_3") (pintype "passive+no_connect"))
    )
    (net (code "73") (name "unconnected-(U2-NC-Pad4)") (class "Default")
      (node (ref "U2") (pin "4") (pinfunction "NC_4") (pintype "passive+no_connect"))
    )
    (net (code "74") (name "unconnected-(U2-NC-Pad5)") (class "Default")
      (node (ref "U2") (pin "5") (pinfunction "NC_5") (pintype "passive+no_connect"))
    )
    (net (code "75") (name "unconnected-(U2-NC-Pad14)") (class "Default")
      (node (ref "U2") (pin "14") (pinfunction "NC_14") (pintype "passive+no_connect"))
    )
    (net (code "76") (name "unconnected-(U2-NC-Pad15)") (class "Default")
      (node (ref "U2") (pin "15") (pinfunction "NC_15") (pintype "passive+no_connect"))
    )
    (net (code "77") (name "unconnected-(U2-NC-Pad16)") (class "Default")
      (node (ref "U2") (pin "16") (pinfunction "NC_16") (pintype "passive+no_connect"))
    )
    (net (code "78") (name "unconnected-(U2-NC-Pad17)") (class "Default")
      (node (ref "U2") (pin "17") (pinfunction "NC_17") (pintype "passive+no_connect"))
    )
    (net (code "79") (name "unconnected-(U2-RESV-Pad19)") (class "Default")
      (node (ref "U2") (pin "19") (pinfunction "RESV_19") (pintype "passive+no_connect"))
    )
    (net (code "80") (name "unconnected-(U2-RESV-Pad21)") (class "Default")
      (node (ref "U2") (pin "21") (pinfunction "RESV_21") (pintype "passive+no_connect"))
    )
    (net (code "81") (name "unconnected-(U6-CSB-Pad2)") (class "Default")
      (node (ref "U6") (pin "2") (pinfunction "CSB_2") (pintype "power_in+no_connect"))
    )
  )
)
